# SurfaceEEG_Hub_V1_0.net
KiCad netlist of a schematic drawn in EAGLE
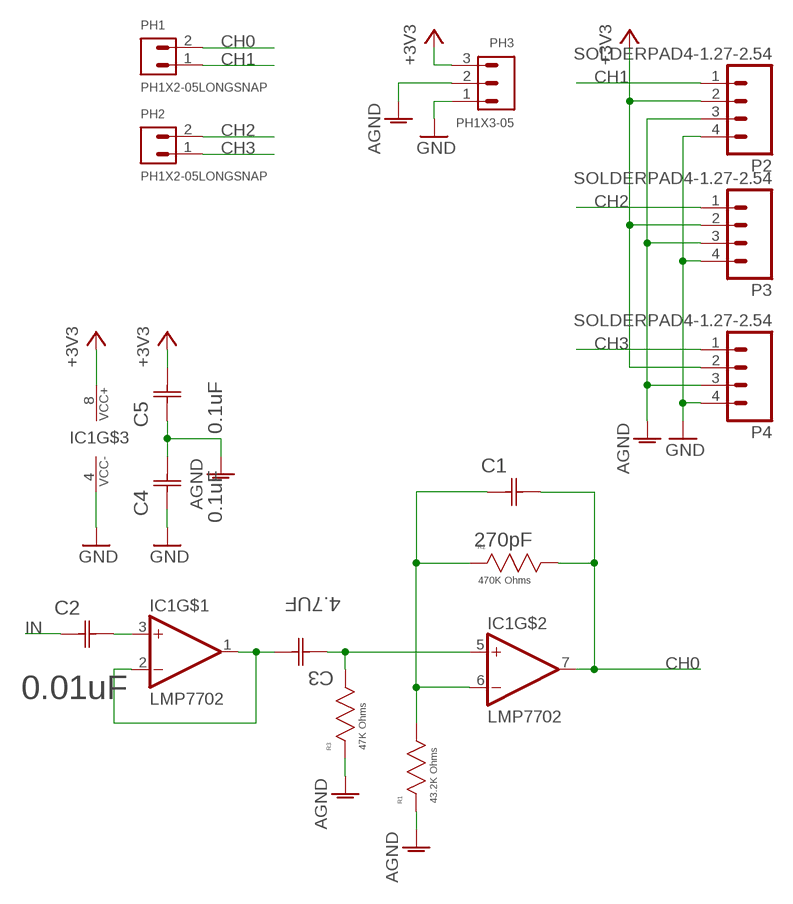
[diagram p0: schematic, sheet 1]

(export (version "E")
  (design (tool "Eeschema 10.0.6"))
  (components
    (comp (ref "C1")
      (value "270pF")
      (footprint "eagle-import:CAPC1608X90N")
      (fields (field (name "MPN") "06035A271JAT2A") (field (name "TOLERANCE") "± 5%"))
      (libsource (lib "eagle-import") (part "06035A271JAT2A"))
    )
    (comp (ref "C2")
      (value "0.01uF")
      (footprint "eagle-import:CAPC1005X60N")
      (fields (field (name "MPN") "C0402C103J3RACTU") (field (name "TOLERANCE") "±5%"))
      (libsource (lib "eagle-import") (part "C0402C103J3RACTU"))
    )
    (comp (ref "C3")
      (value "4.7UF")
      (footprint "eagle-import:CAPC1608X90N")
      (fields (field (name "MPN") "06036D475MAT2A") (field (name "TOLERANCE") "±20%"))
      (libsource (lib "eagle-import") (part "06036D475MAT2A"))
    )
    (comp (ref "C4")
      (value "0.1uF")
      (footprint "eagle-import:CAPC1005X60N")
      (fields (field (name "MPN") "04023C104KAT2A") (field (name "TOLERANCE") "±10%"))
      (libsource (lib "eagle-import") (part "04023C104KAT2A"))
    )
    (comp (ref "C5")
      (value "0.1uF")
      (footprint "eagle-import:CAPC1005X60N")
      (fields (field (name "MPN") "04023C104KAT2A") (field (name "TOLERANCE") "±10%"))
      (libsource (lib "eagle-import") (part "04023C104KAT2A"))
    )
    (comp (ref "IC1")
      (value "LMP7702")
      (footprint "eagle-import:VSSOP8")
      (fields (field (name "MPN") "LMP7702MM/NOPB"))
      (libsource (lib "eagle-import") (part "LMP7702"))
    )
    (comp (ref "P2")
      (value "SOLDERPAD4-1.27-2.54")
      (footprint "eagle-import:SMD1,27-2,54")
      (libsource (lib "eagle-import") (part "SOLDERPAD4-1.27-2.54"))
    )
    (comp (ref "P3")
      (value "SOLDERPAD4-1.27-2.54")
      (footprint "eagle-import:SMD1,27-2,54")
      (libsource (lib "eagle-import") (part "SOLDERPAD4-1.27-2.54"))
    )
    (comp (ref "P4")
      (value "SOLDERPAD4-1.27-2.54")
      (footprint "eagle-import:SMD1,27-2,54")
      (libsource (lib "eagle-import") (part "SOLDERPAD4-1.27-2.54"))
    )
    (comp (ref "PH1")
      (value "PH1X2-05LONGSNAP")
      (footprint "eagle-import:PHLS005-1-2")
      (libsource (lib "eagle-import") (part "PH1X2-05LONGSNAP"))
    )
    (comp (ref "PH2")
      (value "PH1X2-05LONGSNAP")
      (footprint "eagle-import:PHLS005-1-2")
      (libsource (lib "eagle-import") (part "PH1X2-05LONGSNAP"))
    )
    (comp (ref "PH3")
      (value "PH1X3-05")
      (footprint "eagle-import:PH005-1-3")
      (libsource (lib "eagle-import") (part "PH1X3-05"))
    )
    (comp (ref "R1")
      (value "43.2K Ohms")
      (footprint "eagle-import:RESC1608X60N")
      (fields (field (name "MPN") "RC0603FR-0743K2L") (field (name "TOLERANCE") "±1%"))
      (libsource (lib "eagle-import") (part "RC0603FR-0743K2L"))
    )
    (comp (ref "R2")
      (value "470K Ohms")
      (footprint "eagle-import:RESC1608X60N")
      (fields (field (name "MPN") "RC0603FR-07470KL") (field (name "TOLERANCE") "±1%"))
      (libsource (lib "eagle-import") (part "RC0603FR-07470KL"))
    )
    (comp (ref "R3")
      (value "47K Ohms")
      (footprint "eagle-import:RESC1608X60N")
      (fields (field (name "MPN") "RC0603FR-0747KL") (field (name "TOLERANCE") "±1%"))
      (libsource (lib "eagle-import") (part "RC0603FR-0747KL"))
    )
  )
  (nets
    (net (code "1") (name "+3V3") (class "Default")
      (node (ref "C5") (pin "1") (pinfunction "C2_1") (pintype "passive"))
      (node (ref "IC1") (pin "8") (pinfunction "VCC+_8") (pintype "power_in"))
      (node (ref "P2") (pin "2") (pinfunction "2_2") (pintype "passive"))
      (node (ref "P3") (pin "2") (pinfunction "2_2") (pintype "passive"))
      (node (ref "P4") (pin "2") (pinfunction "2_2") (pintype "passive"))
      (node (ref "PH3") (pin "3") (pinfunction "3_3") (pintype "bidirectional"))
    )
    (net (code "2") (name "/CH0") (class "Default")
      (node (ref "C1") (pin "2") (pinfunction "C2_2") (pintype "passive"))
      (node (ref "IC1") (pin "7") (pinfunction "OUT_7") (pintype "output"))
      (node (ref "PH1") (pin "2") (pinfunction "2_2") (pintype "bidirectional"))
      (node (ref "R2") (pin "1") (pinfunction "R1_1") (pintype "passive"))
    )
    (net (code "3") (name "/CH1") (class "Default")
      (node (ref "P2") (pin "1") (pinfunction "1_1") (pintype "passive"))
      (node (ref "PH1") (pin "1") (pinfunction "1_1") (pintype "bidirectional"))
    )
    (net (code "4") (name "/CH2") (class "Default")
      (node (ref "P3") (pin "1") (pinfunction "1_1") (pintype "passive"))
      (node (ref "PH2") (pin "2") (pinfunction "2_2") (pintype "bidirectional"))
    )
    (net (code "5") (name "/CH3") (class "Default")
      (node (ref "P4") (pin "1") (pinfunction "1_1") (pintype "passive"))
      (node (ref "PH2") (pin "1") (pinfunction "1_1") (pintype "bidirectional"))
    )
    (net (code "6") (name "/IN") (class "Default")
      (node (ref "C2") (pin "1") (pinfunction "C1_1") (pintype "passive"))
    )
    (net (code "7") (name "AGND") (class "Default")
      (node (ref "C4") (pin "1") (pinfunction "C2_1") (pintype "passive"))
      (node (ref "C5") (pin "2") (pinfunction "C1_2") (pintype "passive"))
      (node (ref "P2") (pin "3") (pinfunction "3_3") (pintype "passive"))
      (node (ref "P3") (pin "3") (pinfunction "3_3") (pintype "passive"))
      (node (ref "P4") (pin "3") (pinfunction "3_3") (pintype "passive"))
      (node (ref "PH3") (pin "2") (pinfunction "2_2") (pintype "bidirectional"))
      (node (ref "R1") (pin "2") (pinfunction "R2_2") (pintype "passive"))
      (node (ref "R3") (pin "2") (pinfunction "R2_2") (pintype "passive"))
    )
    (net (code "8") (name "GND") (class "Default")
      (node (ref "C4") (pin "2") (pinfunction "C1_2") (pintype "passive"))
      (node (ref "IC1") (pin "4") (pinfunction "VCC-_4") (pintype "power_in"))
      (node (ref "P2") (pin "4") (pinfunction "4_4") (pintype "passive"))
      (node (ref "P3") (pin "4") (pinfunction "4_4") (pintype "passive"))
      (node (ref "P4") (pin "4") (pinfunction "4_4") (pintype "passive"))
      (node (ref "PH3") (pin "1") (pinfunction "1_1") (pintype "bidirectional"))
    )
    (net (code "9") (name "Net-(C1-C1)") (class "Default")
      (node (ref "C1") (pin "1") (pinfunction "C1_1") (pintype "passive"))
      (node (ref "IC1") (pin "6") (pinfunction "IN-_6") (pintype "input"))
      (node (ref "R1") (pin "1") (pinfunction "R1_1") (pintype "passive"))
      (node (ref "R2") (pin "2") (pinfunction "R2_2") (pintype "passive"))
    )
    (net (code "10") (name "Net-(C2-C2)") (class "Default")
      (node (ref "C2") (pin "2") (pinfunction "C2_2") (pintype "passive"))
      (node (ref "IC1") (pin "3") (pinfunction "IN+_3") (pintype "input"))
    )
    (net (code "11") (name "Net-(C3-C1)") (class "Default")
      (node (ref "C3") (pin "1") (pinfunction "C1_1") (pintype "passive"))
      (node (ref "IC1") (pin "5") (pinfunction "IN+_5") (pintype "input"))
      (node (ref "R3") (pin "1") (pinfunction "R1_1") (pintype "passive"))
    )
    (net (code "12") (name "Net-(C3-C2)") (class "Default")
      (node (ref "C3") (pin "2") (pinfunction "C2_2") (pintype "passive"))
      (node (ref "IC1") (pin "1") (pinfunction "OUT_1") (pintype "output"))
      (node (ref "IC1") (pin "2") (pinfunction "IN-_2") (pintype "input"))
    )
  )
)
